# Button_Board.net
KiCad netlist of a schematic drawn in EasyEDA
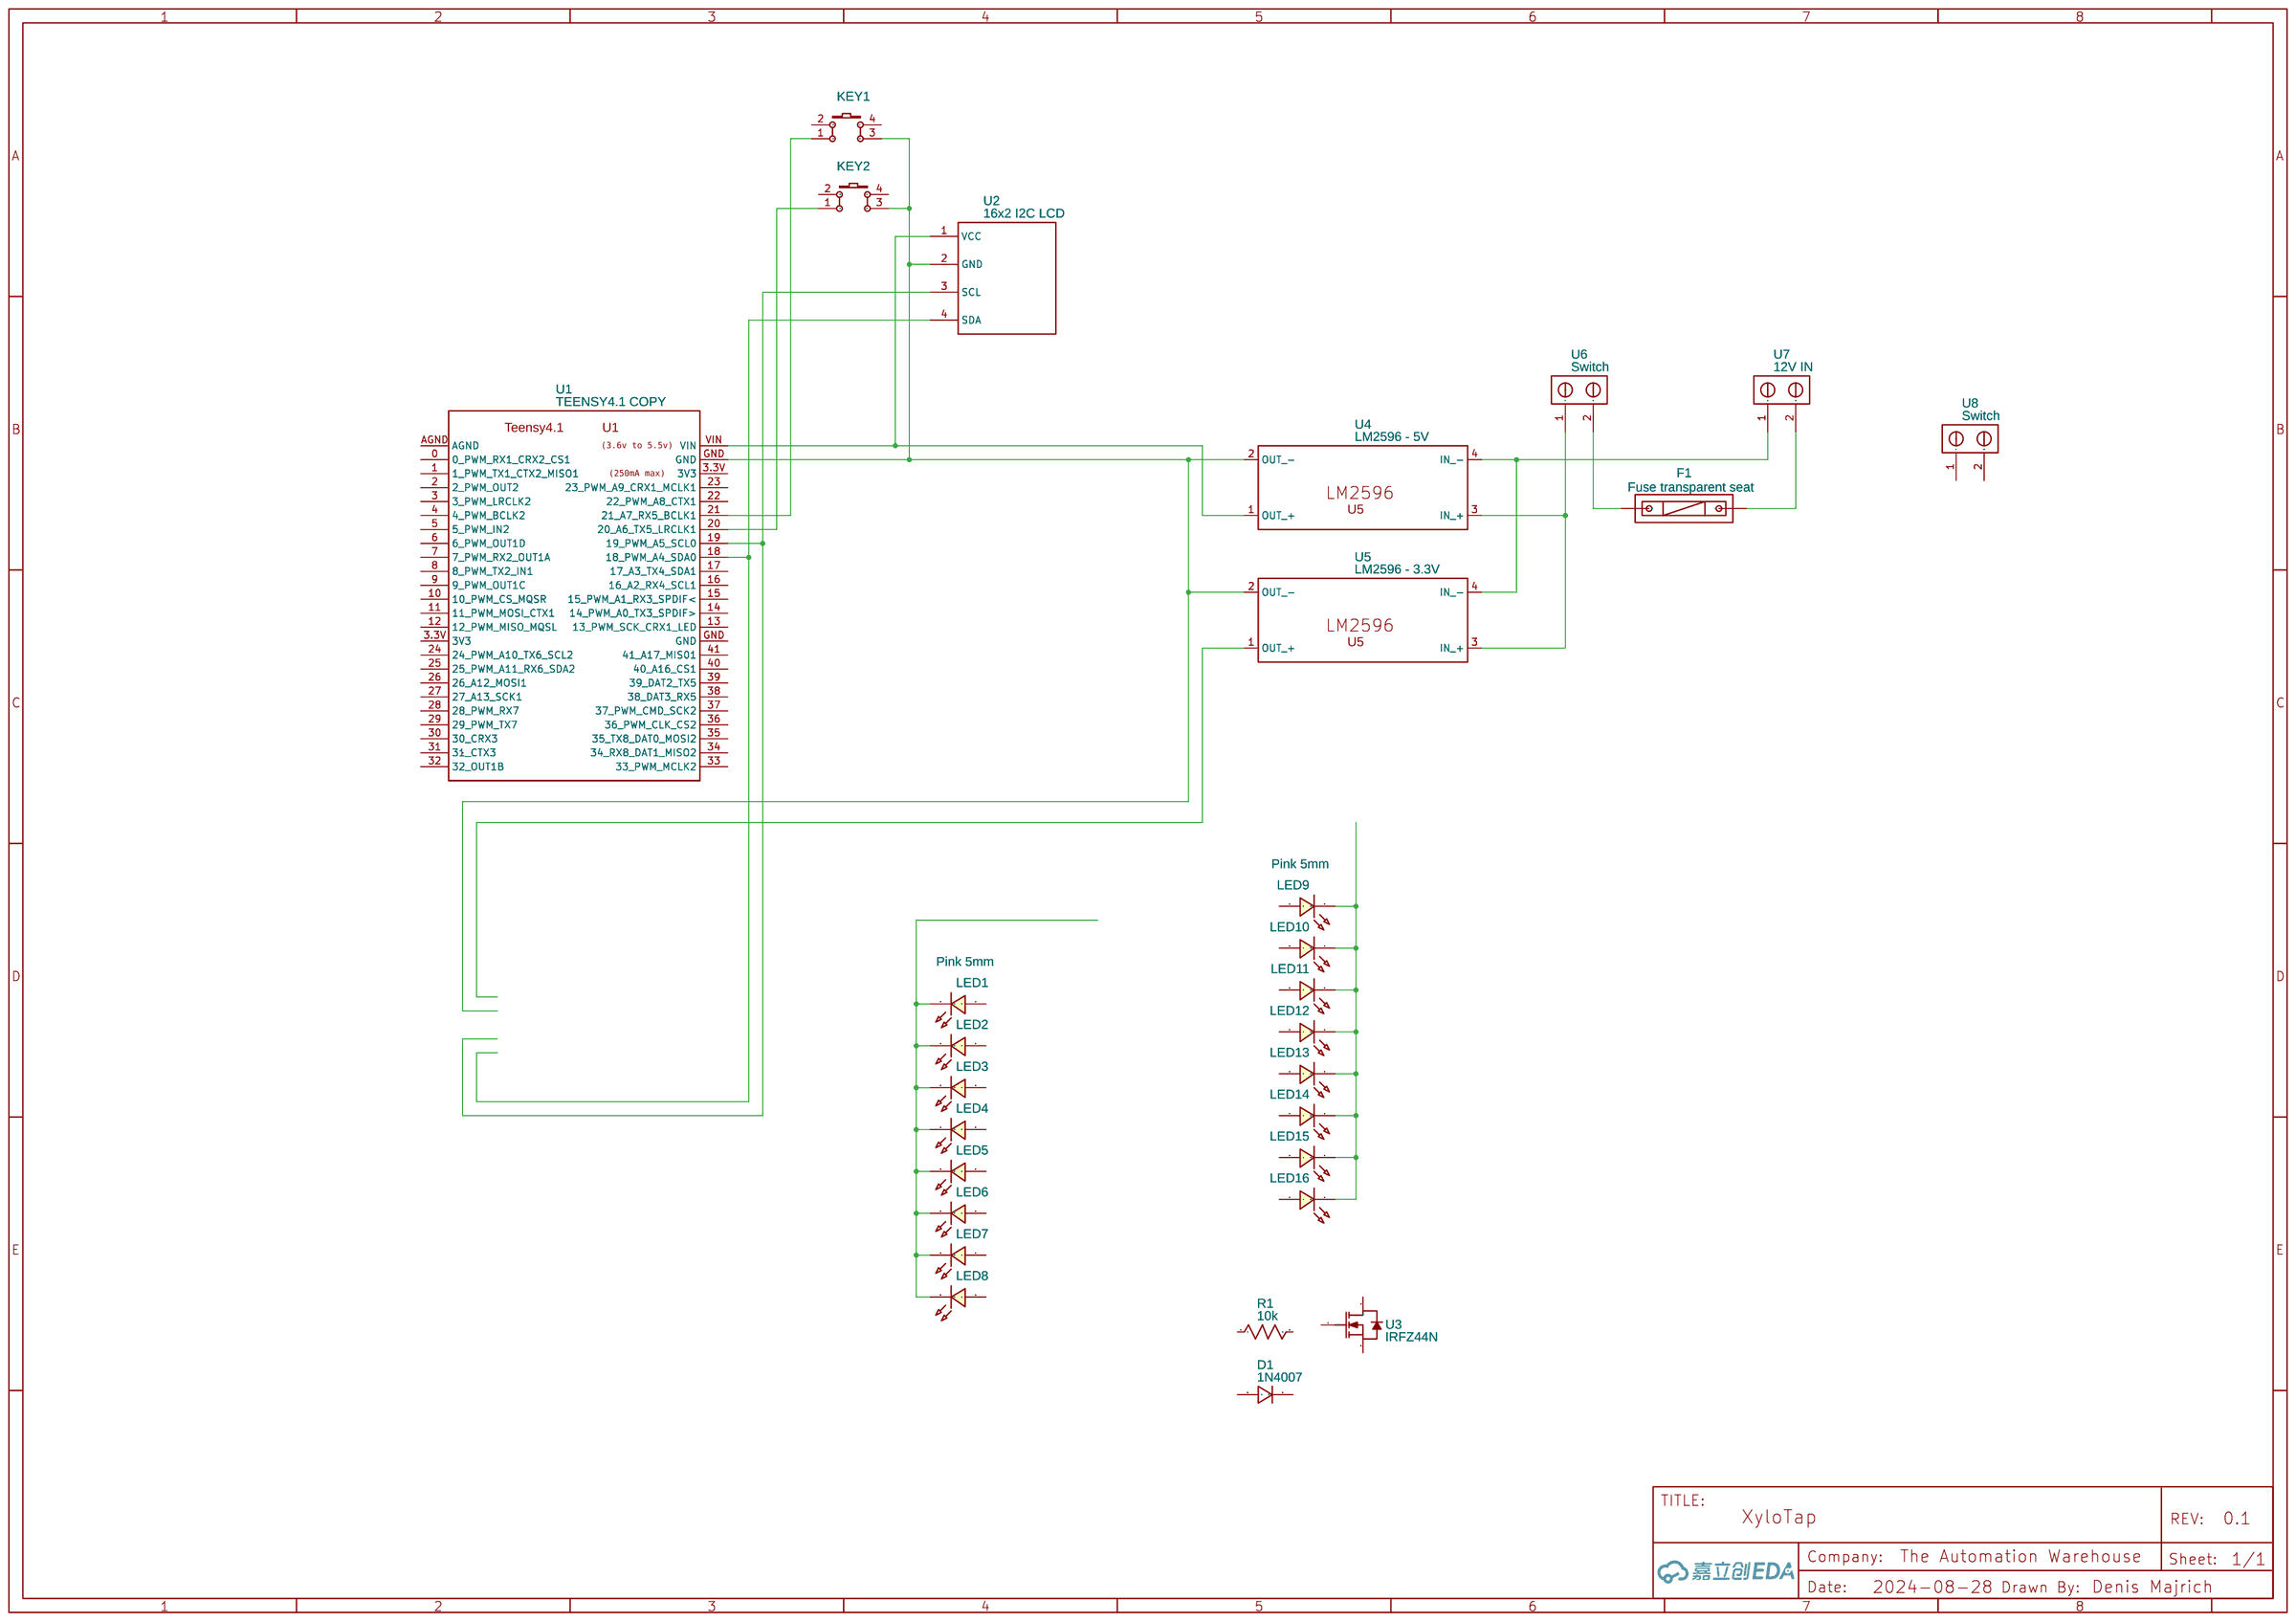
[diagram p0: Controller]
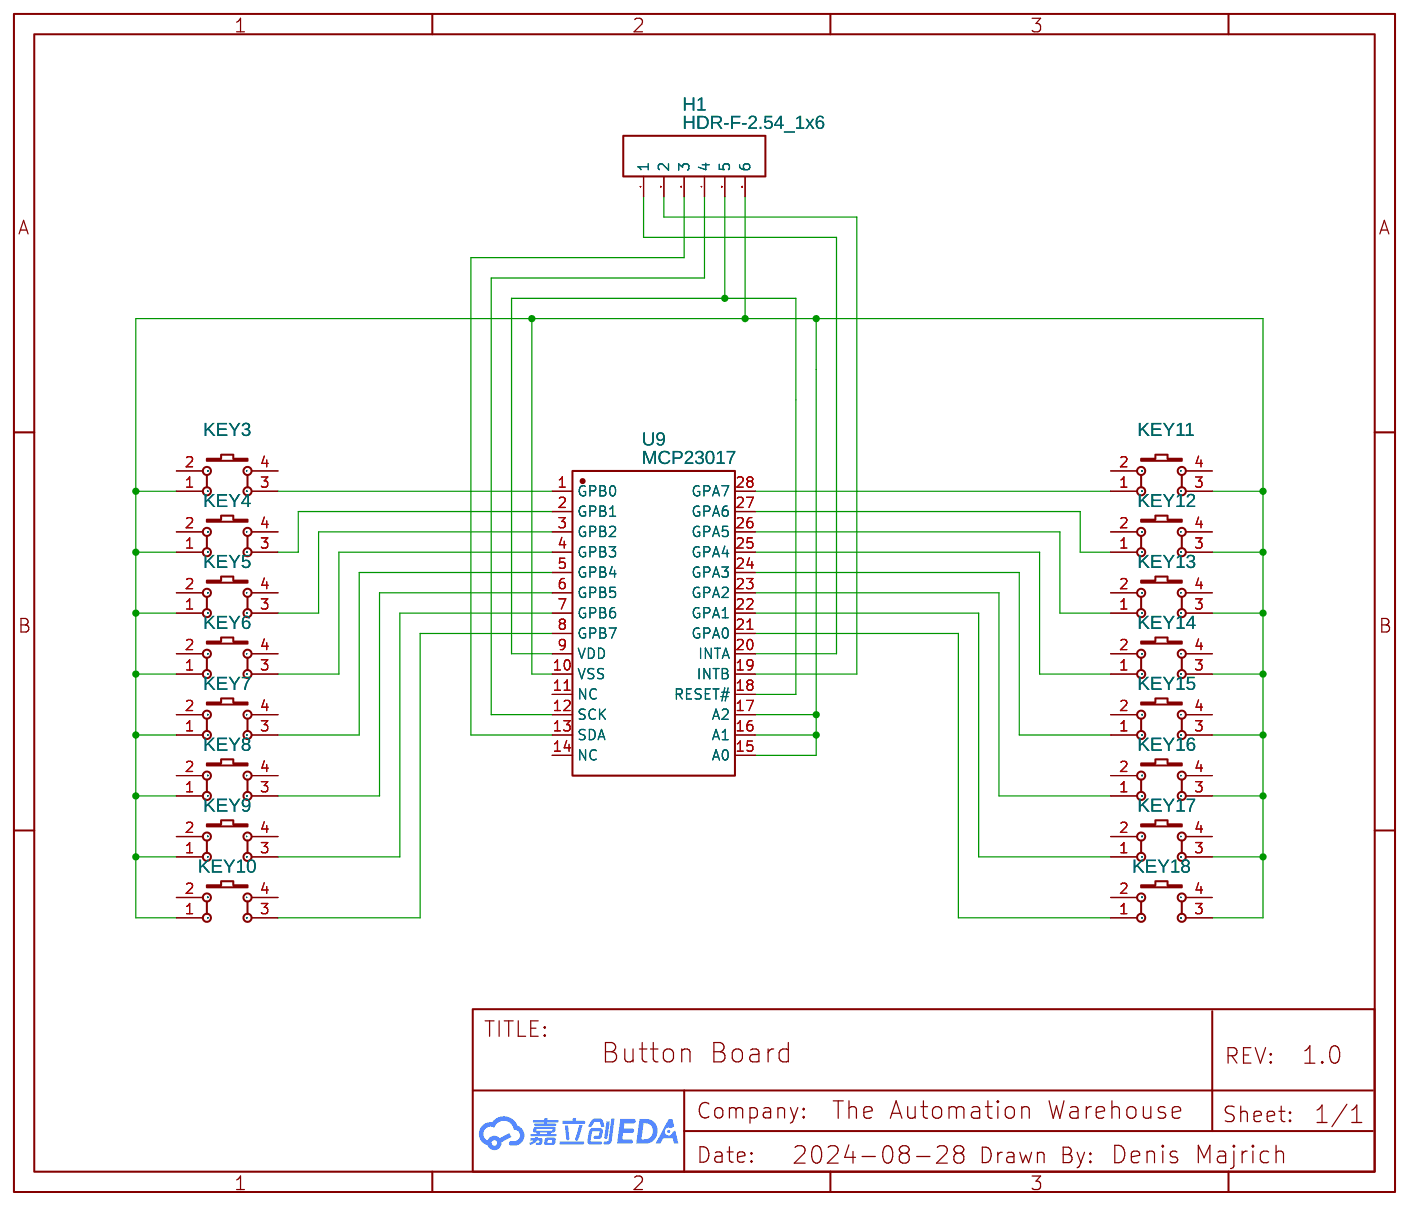
[diagram p1: Button Board]

(export (version "E")
  (design (tool "Eeschema 10.0.6"))
  (components
    (comp (ref "D1")
      (value "1N4007")
      (fields (field (name "BOM_Supplier Part") "C106903"))
      (libsource (lib "") (part "1N4007"))
    )
    (comp (ref "F1")
      (value "Fuse transparent seat")
      (fields (field (name "Manufacturer Part") "保险丝透明座") (field (name "Manufacturer") "xcfuse(旭程)"))
      (libsource (lib "") (part "Fuse transparent seat"))
    )
    (comp (ref "KEY1")
      (value "K4-12×12_TH")
      (fields
        (field (name "BOM_Manufacturer Part") "K2-1103DP-M4SW-04")
        (field (name "BOM_Supplier Part") "C128053")
      )
      (libsource (lib "") (part "K4-12×12_TH"))
    )
    (comp (ref "KEY2")
      (value "K4-12×12_TH")
      (fields
        (field (name "BOM_Manufacturer Part") "K2-1103DP-M4SW-04")
        (field (name "BOM_Supplier Part") "C128053")
      )
      (libsource (lib "") (part "K4-12×12_TH"))
    )
    (comp (ref "LED1") (value "Pink 5mm") (libsource (lib "") (part "LED-TH-5mm_B_1")))
    (comp (ref "LED2") (value "Pink 5mm") (libsource (lib "") (part "LED-TH-5mm_B_1")))
    (comp (ref "LED3") (value "Pink 5mm") (libsource (lib "") (part "LED-TH-5mm_B_1")))
    (comp (ref "LED4") (value "Pink 5mm") (libsource (lib "") (part "LED-TH-5mm_B_1")))
    (comp (ref "LED5") (value "Pink 5mm") (libsource (lib "") (part "LED-TH-5mm_B_1")))
    (comp (ref "LED6") (value "Pink 5mm") (libsource (lib "") (part "LED-TH-5mm_B_1")))
    (comp (ref "LED7") (value "Pink 5mm") (libsource (lib "") (part "LED-TH-5mm_B_1")))
    (comp (ref "LED8") (value "Pink 5mm") (libsource (lib "") (part "LED-TH-5mm_B_1")))
    (comp (ref "LED9") (value "Pink 5mm") (libsource (lib "") (part "LED-TH-5mm_B")))
    (comp (ref "LED10") (value "Pink 5mm") (libsource (lib "") (part "LED-TH-5mm_B")))
    (comp (ref "LED11") (value "Pink 5mm") (libsource (lib "") (part "LED-TH-5mm_B")))
    (comp (ref "LED12") (value "Pink 5mm") (libsource (lib "") (part "LED-TH-5mm_B")))
    (comp (ref "LED13") (value "Pink 5mm") (libsource (lib "") (part "LED-TH-5mm_B")))
    (comp (ref "LED14") (value "Pink 5mm") (libsource (lib "") (part "LED-TH-5mm_B")))
    (comp (ref "LED15") (value "Pink 5mm") (libsource (lib "") (part "LED-TH-5mm_B")))
    (comp (ref "LED16") (value "Pink 5mm") (libsource (lib "") (part "LED-TH-5mm_B")))
    (comp (ref "R1") (value "10k") (libsource (lib "") (part "R_AXIAL-0.4_US")))
    (comp (ref "U1")
      (value "TEENSY4.1 COPY")
      (fields (field (name "BOM_Manufacturer Part") "Teensy4.1"))
      (libsource (lib "") (part "TEENSY4.1 COPY"))
    )
    (comp (ref "U2") (value "16x2 I2C LCD") (libsource (lib "") (part "16x2 i2c LCD no mount on PCB")))
    (comp (ref "U3")
      (value "IRFZ44N")
      (fields (field (name "Manufacturer") "minos(迈诺斯)"))
      (libsource (lib "") (part "IRFZ44N"))
    )
    (comp (ref "U4")
      (value "LM2596 - 5V")
      (fields (field (name "BOM_Manufacturer Part") "LM2596ALEX"))
      (libsource (lib "") (part "LM2596ALEX"))
    )
    (comp (ref "U5")
      (value "LM2596 - 3.3V")
      (fields (field (name "BOM_Manufacturer Part") "LM2596ALEX"))
      (libsource (lib "") (part "LM2596ALEX"))
    )
    (comp (ref "U6") (value "Switch") (libsource (lib "") (part "Terminal_x2_5mm")))
    (comp (ref "U7") (value "12V IN") (libsource (lib "") (part "Terminal_x2_5mm")))
    (comp (ref "U8") (value "Switch") (libsource (lib "") (part "Terminal_x2_5mm")))
    (comp (ref "H1")
      (value "HDR-F-2.54_1x6")
      (fields (field (name "BOM_Supplier Part") "C40877"))
      (libsource (lib "") (part "HDR-F-2.54_1x6"))
    )
    (comp (ref "KEY3")
      (value "K4-12×12_TH")
      (fields
        (field (name "BOM_Manufacturer Part") "K2-1103DP-M4SW-04")
        (field (name "BOM_Supplier Part") "C128053")
      )
      (libsource (lib "") (part "K4-12×12_TH"))
    )
    (comp (ref "KEY4")
      (value "K4-12×12_TH")
      (fields
        (field (name "BOM_Manufacturer Part") "K2-1103DP-M4SW-04")
        (field (name "BOM_Supplier Part") "C128053")
      )
      (libsource (lib "") (part "K4-12×12_TH"))
    )
    (comp (ref "KEY5")
      (value "K4-12×12_TH")
      (fields
        (field (name "BOM_Manufacturer Part") "K2-1103DP-M4SW-04")
        (field (name "BOM_Supplier Part") "C128053")
      )
      (libsource (lib "") (part "K4-12×12_TH"))
    )
    (comp (ref "KEY6")
      (value "K4-12×12_TH")
      (fields
        (field (name "BOM_Manufacturer Part") "K2-1103DP-M4SW-04")
        (field (name "BOM_Supplier Part") "C128053")
      )
      (libsource (lib "") (part "K4-12×12_TH"))
    )
    (comp (ref "KEY7")
      (value "K4-12×12_TH")
      (fields
        (field (name "BOM_Manufacturer Part") "K2-1103DP-M4SW-04")
        (field (name "BOM_Supplier Part") "C128053")
      )
      (libsource (lib "") (part "K4-12×12_TH"))
    )
    (comp (ref "KEY8")
      (value "K4-12×12_TH")
      (fields
        (field (name "BOM_Manufacturer Part") "K2-1103DP-M4SW-04")
        (field (name "BOM_Supplier Part") "C128053")
      )
      (libsource (lib "") (part "K4-12×12_TH"))
    )
    (comp (ref "KEY9")
      (value "K4-12×12_TH")
      (fields
        (field (name "BOM_Manufacturer Part") "K2-1103DP-M4SW-04")
        (field (name "BOM_Supplier Part") "C128053")
      )
      (libsource (lib "") (part "K4-12×12_TH"))
    )
    (comp (ref "KEY10")
      (value "K4-12×12_TH")
      (fields
        (field (name "BOM_Manufacturer Part") "K2-1103DP-M4SW-04")
        (field (name "BOM_Supplier Part") "C128053")
      )
      (libsource (lib "") (part "K4-12×12_TH"))
    )
    (comp (ref "KEY11")
      (value "K4-12×12_TH")
      (fields
        (field (name "BOM_Manufacturer Part") "K2-1103DP-M4SW-04")
        (field (name "BOM_Supplier Part") "C128053")
      )
      (libsource (lib "") (part "K4-12×12_TH"))
    )
    (comp (ref "KEY12")
      (value "K4-12×12_TH")
      (fields
        (field (name "BOM_Manufacturer Part") "K2-1103DP-M4SW-04")
        (field (name "BOM_Supplier Part") "C128053")
      )
      (libsource (lib "") (part "K4-12×12_TH"))
    )
    (comp (ref "KEY13")
      (value "K4-12×12_TH")
      (fields
        (field (name "BOM_Manufacturer Part") "K2-1103DP-M4SW-04")
        (field (name "BOM_Supplier Part") "C128053")
      )
      (libsource (lib "") (part "K4-12×12_TH"))
    )
    (comp (ref "KEY14")
      (value "K4-12×12_TH")
      (fields
        (field (name "BOM_Manufacturer Part") "K2-1103DP-M4SW-04")
        (field (name "BOM_Supplier Part") "C128053")
      )
      (libsource (lib "") (part "K4-12×12_TH"))
    )
    (comp (ref "KEY15")
      (value "K4-12×12_TH")
      (fields
        (field (name "BOM_Manufacturer Part") "K2-1103DP-M4SW-04")
        (field (name "BOM_Supplier Part") "C128053")
      )
      (libsource (lib "") (part "K4-12×12_TH"))
    )
    (comp (ref "KEY16")
      (value "K4-12×12_TH")
      (fields
        (field (name "BOM_Manufacturer Part") "K2-1103DP-M4SW-04")
        (field (name "BOM_Supplier Part") "C128053")
      )
      (libsource (lib "") (part "K4-12×12_TH"))
    )
    (comp (ref "KEY17")
      (value "K4-12×12_TH")
      (fields
        (field (name "BOM_Manufacturer Part") "K2-1103DP-M4SW-04")
        (field (name "BOM_Supplier Part") "C128053")
      )
      (libsource (lib "") (part "K4-12×12_TH"))
    )
    (comp (ref "KEY18")
      (value "K4-12×12_TH")
      (fields
        (field (name "BOM_Manufacturer Part") "K2-1103DP-M4SW-04")
        (field (name "BOM_Supplier Part") "C128053")
      )
      (libsource (lib "") (part "K4-12×12_TH"))
    )
    (comp (ref "U9")
      (value "MCP23017")
      (fields
        (field (name "Manufacturer Part") "MCP23017-E/SP")
        (field (name "Manufacturer") "MICROCHIP(美国微芯)")
      )
      (libsource (lib "") (part "MCP23017-E/SP"))
    )
  )
  (nets
    (net (code "1") (name "Net-(F1-Pad1)") (class "Default")
      (node (ref "F1") (pin "1") (pinfunction "1_1") (pintype "unspecified"))
      (node (ref "U7") (pin "2") (pinfunction "2_2") (pintype "unspecified"))
    )
    (net (code "2") (name "Net-(F1-Pad2)") (class "Default")
      (node (ref "F1") (pin "2") (pinfunction "2_2") (pintype "unspecified"))
      (node (ref "U6") (pin "2") (pinfunction "2_2") (pintype "unspecified"))
    )
    (net (code "3") (name "Net-(LED1-Pad2)") (class "Default")
      (node (ref "LED1") (pin "2") (pinfunction "2_2") (pintype "unspecified"))
      (node (ref "LED2") (pin "2") (pinfunction "2_2") (pintype "unspecified"))
      (node (ref "LED3") (pin "2") (pinfunction "2_2") (pintype "unspecified"))
      (node (ref "LED4") (pin "2") (pinfunction "2_2") (pintype "unspecified"))
      (node (ref "LED5") (pin "2") (pinfunction "2_2") (pintype "unspecified"))
      (node (ref "LED6") (pin "2") (pinfunction "2_2") (pintype "unspecified"))
      (node (ref "LED7") (pin "2") (pinfunction "2_2") (pintype "unspecified"))
      (node (ref "LED8") (pin "2") (pinfunction "2_2") (pintype "unspecified"))
    )
    (net (code "4") (name "Net-(LED10-Pad2)") (class "Default")
      (node (ref "LED10") (pin "2") (pinfunction "2_2") (pintype "unspecified"))
      (node (ref "LED11") (pin "2") (pinfunction "2_2") (pintype "unspecified"))
      (node (ref "LED12") (pin "2") (pinfunction "2_2") (pintype "unspecified"))
      (node (ref "LED13") (pin "2") (pinfunction "2_2") (pintype "unspecified"))
      (node (ref "LED14") (pin "2") (pinfunction "2_2") (pintype "unspecified"))
      (node (ref "LED15") (pin "2") (pinfunction "2_2") (pintype "unspecified"))
      (node (ref "LED16") (pin "2") (pinfunction "2_2") (pintype "unspecified"))
      (node (ref "LED9") (pin "2") (pinfunction "2_2") (pintype "unspecified"))
    )
    (net (code "5") (name "Net-(U1-18_PWM_A4_SDA0)") (class "Default")
      (node (ref "U1") (pin "18") (pinfunction "18_PWM_A4_SDA0_18") (pintype "bidirectional"))
      (node (ref "U2") (pin "4") (pinfunction "SDA_4") (pintype "unspecified"))
    )
    (net (code "6") (name "Net-(U1-19_PWM_A5_SCL0)") (class "Default")
      (node (ref "U1") (pin "19") (pinfunction "19_PWM_A5_SCL0_19") (pintype "bidirectional"))
      (node (ref "U2") (pin "3") (pinfunction "SCL_3") (pintype "unspecified"))
    )
    (net (code "7") (name "Net-(U1-20_A6_TX5_LRCLK1)") (class "Default")
      (node (ref "KEY2") (pin "1") (pinfunction "1_1") (pintype "unspecified"))
      (node (ref "U1") (pin "20") (pinfunction "20_A6_TX5_LRCLK1_20") (pintype "bidirectional"))
    )
    (net (code "8") (name "Net-(U1-21_A7_RX5_BCLK1)") (class "Default")
      (node (ref "KEY1") (pin "1") (pinfunction "1_1") (pintype "unspecified"))
      (node (ref "U1") (pin "21") (pinfunction "21_A7_RX5_BCLK1_21") (pintype "bidirectional"))
    )
    (net (code "9") (name "Net-(U2-GND)") (class "Default")
      (node (ref "KEY1") (pin "3") (pinfunction "3_3") (pintype "unspecified"))
      (node (ref "KEY2") (pin "3") (pinfunction "3_3") (pintype "unspecified"))
      (node (ref "U1") (pin "GND") (pinfunction "GND_GND") (pintype "bidirectional"))
      (node (ref "U2") (pin "2") (pinfunction "GND_2") (pintype "unspecified"))
      (node (ref "U4") (pin "2") (pinfunction "OUT_-_2") (pintype "unspecified"))
      (node (ref "U5") (pin "2") (pinfunction "OUT_-_2") (pintype "unspecified"))
    )
    (net (code "10") (name "Net-(U2-VCC)") (class "Default")
      (node (ref "U1") (pin "VIN") (pinfunction "VIN_VIN") (pintype "bidirectional"))
      (node (ref "U2") (pin "1") (pinfunction "VCC_1") (pintype "unspecified"))
      (node (ref "U4") (pin "1") (pinfunction "OUT_+_1") (pintype "unspecified"))
    )
    (net (code "11") (name "Net-(U4-IN_+)") (class "Default")
      (node (ref "U4") (pin "3") (pinfunction "IN_+_3") (pintype "unspecified"))
      (node (ref "U5") (pin "3") (pinfunction "IN_+_3") (pintype "unspecified"))
      (node (ref "U6") (pin "1") (pinfunction "1_1") (pintype "unspecified"))
    )
    (net (code "12") (name "Net-(U4-IN_-)") (class "Default")
      (node (ref "U4") (pin "4") (pinfunction "IN_-_4") (pintype "unspecified"))
      (node (ref "U5") (pin "4") (pinfunction "IN_-_4") (pintype "unspecified"))
      (node (ref "U7") (pin "1") (pinfunction "1_1") (pintype "unspecified"))
    )
    (net (code "13") (name "Net-(U9-A0)") (class "Default")
      (node (ref "H1") (pin "6") (pinfunction "6_6") (pintype "input"))
      (node (ref "KEY10") (pin "1") (pinfunction "1_1") (pintype "unspecified"))
      (node (ref "KEY11") (pin "3") (pinfunction "3_3") (pintype "unspecified"))
      (node (ref "KEY12") (pin "3") (pinfunction "3_3") (pintype "unspecified"))
      (node (ref "KEY13") (pin "3") (pinfunction "3_3") (pintype "unspecified"))
      (node (ref "KEY14") (pin "3") (pinfunction "3_3") (pintype "unspecified"))
      (node (ref "KEY15") (pin "3") (pinfunction "3_3") (pintype "unspecified"))
      (node (ref "KEY16") (pin "3") (pinfunction "3_3") (pintype "unspecified"))
      (node (ref "KEY17") (pin "3") (pinfunction "3_3") (pintype "unspecified"))
      (node (ref "KEY18") (pin "3") (pinfunction "3_3") (pintype "unspecified"))
      (node (ref "KEY3") (pin "1") (pinfunction "1_1") (pintype "unspecified"))
      (node (ref "KEY4") (pin "1") (pinfunction "1_1") (pintype "unspecified"))
      (node (ref "KEY5") (pin "1") (pinfunction "1_1") (pintype "unspecified"))
      (node (ref "KEY6") (pin "1") (pinfunction "1_1") (pintype "unspecified"))
      (node (ref "KEY7") (pin "1") (pinfunction "1_1") (pintype "unspecified"))
      (node (ref "KEY8") (pin "1") (pinfunction "1_1") (pintype "unspecified"))
      (node (ref "KEY9") (pin "1") (pinfunction "1_1") (pintype "unspecified"))
      (node (ref "U9") (pin "10") (pinfunction "VSS_10") (pintype "unspecified"))
      (node (ref "U9") (pin "15") (pinfunction "A0_15") (pintype "unspecified"))
      (node (ref "U9") (pin "16") (pinfunction "A1_16") (pintype "unspecified"))
      (node (ref "U9") (pin "17") (pinfunction "A2_17") (pintype "unspecified"))
    )
    (net (code "14") (name "Net-(U9-GPA0)") (class "Default")
      (node (ref "KEY18") (pin "1") (pinfunction "1_1") (pintype "unspecified"))
      (node (ref "U9") (pin "21") (pinfunction "GPA0_21") (pintype "unspecified"))
    )
    (net (code "15") (name "Net-(U9-GPA1)") (class "Default")
      (node (ref "KEY17") (pin "1") (pinfunction "1_1") (pintype "unspecified"))
      (node (ref "U9") (pin "22") (pinfunction "GPA1_22") (pintype "unspecified"))
    )
    (net (code "16") (name "Net-(U9-GPA2)") (class "Default")
      (node (ref "KEY16") (pin "1") (pinfunction "1_1") (pintype "unspecified"))
      (node (ref "U9") (pin "23") (pinfunction "GPA2_23") (pintype "unspecified"))
    )
    (net (code "17") (name "Net-(U9-GPA3)") (class "Default")
      (node (ref "KEY15") (pin "1") (pinfunction "1_1") (pintype "unspecified"))
      (node (ref "U9") (pin "24") (pinfunction "GPA3_24") (pintype "unspecified"))
    )
    (net (code "18") (name "Net-(U9-GPA4)") (class "Default")
      (node (ref "KEY14") (pin "1") (pinfunction "1_1") (pintype "unspecified"))
      (node (ref "U9") (pin "25") (pinfunction "GPA4_25") (pintype "unspecified"))
    )
    (net (code "19") (name "Net-(U9-GPA5)") (class "Default")
      (node (ref "KEY13") (pin "1") (pinfunction "1_1") (pintype "unspecified"))
      (node (ref "U9") (pin "26") (pinfunction "GPA5_26") (pintype "unspecified"))
    )
    (net (code "20") (name "Net-(U9-GPA6)") (class "Default")
      (node (ref "KEY12") (pin "1") (pinfunction "1_1") (pintype "unspecified"))
      (node (ref "U9") (pin "27") (pinfunction "GPA6_27") (pintype "unspecified"))
    )
    (net (code "21") (name "Net-(U9-GPA7)") (class "Default")
      (node (ref "KEY11") (pin "1") (pinfunction "1_1") (pintype "unspecified"))
      (node (ref "U9") (pin "28") (pinfunction "GPA7_28") (pintype "unspecified"))
    )
    (net (code "22") (name "Net-(U9-GPB0)") (class "Default")
      (node (ref "KEY3") (pin "3") (pinfunction "3_3") (pintype "unspecified"))
      (node (ref "U9") (pin "1") (pinfunction "GPB0_1") (pintype "unspecified"))
    )
    (net (code "23") (name "Net-(U9-GPB1)") (class "Default")
      (node (ref "KEY4") (pin "3") (pinfunction "3_3") (pintype "unspecified"))
      (node (ref "U9") (pin "2") (pinfunction "GPB1_2") (pintype "unspecified"))
    )
    (net (code "24") (name "Net-(U9-GPB2)") (class "Default")
      (node (ref "KEY5") (pin "3") (pinfunction "3_3") (pintype "unspecified"))
      (node (ref "U9") (pin "3") (pinfunction "GPB2_3") (pintype "unspecified"))
    )
    (net (code "25") (name "Net-(U9-GPB3)") (class "Default")
      (node (ref "KEY6") (pin "3") (pinfunction "3_3") (pintype "unspecified"))
      (node (ref "U9") (pin "4") (pinfunction "GPB3_4") (pintype "unspecified"))
    )
    (net (code "26") (name "Net-(U9-GPB4)") (class "Default")
      (node (ref "KEY7") (pin "3") (pinfunction "3_3") (pintype "unspecified"))
      (node (ref "U9") (pin "5") (pinfunction "GPB4_5") (pintype "unspecified"))
    )
    (net (code "27") (name "Net-(U9-GPB5)") (class "Default")
      (node (ref "KEY8") (pin "3") (pinfunction "3_3") (pintype "unspecified"))
      (node (ref "U9") (pin "6") (pinfunction "GPB5_6") (pintype "unspecified"))
    )
    (net (code "28") (name "Net-(U9-GPB6)") (class "Default")
      (node (ref "KEY9") (pin "3") (pinfunction "3_3") (pintype "unspecified"))
      (node (ref "U9") (pin "7") (pinfunction "GPB6_7") (pintype "unspecified"))
    )
    (net (code "29") (name "Net-(U9-GPB7)") (class "Default")
      (node (ref "KEY10") (pin "3") (pinfunction "3_3") (pintype "unspecified"))
      (node (ref "U9") (pin "8") (pinfunction "GPB7_8") (pintype "unspecified"))
    )
    (net (code "30") (name "Net-(U9-INTA)") (class "Default")
      (node (ref "H1") (pin "1") (pinfunction "1_1") (pintype "input"))
      (node (ref "U9") (pin "20") (pinfunction "INTA_20") (pintype "unspecified"))
    )
    (net (code "31") (name "Net-(U9-INTB)") (class "Default")
      (node (ref "H1") (pin "2") (pinfunction "2_2") (pintype "input"))
      (node (ref "U9") (pin "19") (pinfunction "INTB_19") (pintype "unspecified"))
    )
    (net (code "32") (name "Net-(U9-RESET#)") (class "Default")
      (node (ref "H1") (pin "5") (pinfunction "5_5") (pintype "input"))
      (node (ref "U9") (pin "18") (pinfunction "RESET#_18") (pintype "unspecified"))
      (node (ref "U9") (pin "9") (pinfunction "VDD_9") (pintype "unspecified"))
    )
    (net (code "33") (name "Net-(U9-SCK)") (class "Default")
      (node (ref "H1") (pin "4") (pinfunction "4_4") (pintype "input"))
      (node (ref "U9") (pin "12") (pinfunction "SCK_12") (pintype "unspecified"))
    )
    (net (code "34") (name "Net-(U9-SDA)") (class "Default")
      (node (ref "H1") (pin "3") (pinfunction "3_3") (pintype "input"))
      (node (ref "U9") (pin "13") (pinfunction "SDA_13") (pintype "unspecified"))
    )
    (net (code "35") (name "unconnected-(D1-Pad1)") (class "Default")
      (node (ref "D1") (pin "1") (pinfunction "1_1") (pintype "unspecified"))
    )
    (net (code "36") (name "unconnected-(D1-Pad2)") (class "Default")
      (node (ref "D1") (pin "2") (pinfunction "2_2") (pintype "unspecified"))
    )
    (net (code "37") (name "unconnected-(KEY1-Pad2)") (class "Default")
      (node (ref "KEY1") (pin "2") (pinfunction "2_2") (pintype "unspecified"))
    )
    (net (code "38") (name "unconnected-(KEY1-Pad4)") (class "Default")
      (node (ref "KEY1") (pin "4") (pinfunction "4_4") (pintype "unspecified"))
    )
    (net (code "39") (name "unconnected-(KEY2-Pad2)") (class "Default")
      (node (ref "KEY2") (pin "2") (pinfunction "2_2") (pintype "unspecified"))
    )
    (net (code "40") (name "unconnected-(KEY2-Pad4)") (class "Default")
      (node (ref "KEY2") (pin "4") (pinfunction "4_4") (pintype "unspecified"))
    )
    (net (code "41") (name "unconnected-(KEY3-Pad2)") (class "Default")
      (node (ref "KEY3") (pin "2") (pinfunction "2_2") (pintype "unspecified"))
    )
    (net (code "42") (name "unconnected-(KEY3-Pad4)") (class "Default")
      (node (ref "KEY3") (pin "4") (pinfunction "4_4") (pintype "unspecified"))
    )
    (net (code "43") (name "unconnected-(KEY4-Pad2)") (class "Default")
      (node (ref "KEY4") (pin "2") (pinfunction "2_2") (pintype "unspecified"))
    )
    (net (code "44") (name "unconnected-(KEY4-Pad4)") (class "Default")
      (node (ref "KEY4") (pin "4") (pinfunction "4_4") (pintype "unspecified"))
    )
    (net (code "45") (name "unconnected-(KEY5-Pad2)") (class "Default")
      (node (ref "KEY5") (pin "2") (pinfunction "2_2") (pintype "unspecified"))
    )
    (net (code "46") (name "unconnected-(KEY5-Pad4)") (class "Default")
      (node (ref "KEY5") (pin "4") (pinfunction "4_4") (pintype "unspecified"))
    )
    (net (code "47") (name "unconnected-(KEY6-Pad2)") (class "Default")
      (node (ref "KEY6") (pin "2") (pinfunction "2_2") (pintype "unspecified"))
    )
    (net (code "48") (name "unconnected-(KEY6-Pad4)") (class "Default")
      (node (ref "KEY6") (pin "4") (pinfunction "4_4") (pintype "unspecified"))
    )
    (net (code "49") (name "unconnected-(KEY7-Pad2)") (class "Default")
      (node (ref "KEY7") (pin "2") (pinfunction "2_2") (pintype "unspecified"))
    )
    (net (code "50") (name "unconnected-(KEY7-Pad4)") (class "Default")
      (node (ref "KEY7") (pin "4") (pinfunction "4_4") (pintype "unspecified"))
    )
    (net (code "51") (name "unconnected-(KEY8-Pad2)") (class "Default")
      (node (ref "KEY8") (pin "2") (pinfunction "2_2") (pintype "unspecified"))
    )
    (net (code "52") (name "unconnected-(KEY8-Pad4)") (class "Default")
      (node (ref "KEY8") (pin "4") (pinfunction "4_4") (pintype "unspecified"))
    )
    (net (code "53") (name "unconnected-(KEY9-Pad2)") (class "Default")
      (node (ref "KEY9") (pin "2") (pinfunction "2_2") (pintype "unspecified"))
    )
    (net (code "54") (name "unconnected-(KEY9-Pad4)") (class "Default")
      (node (ref "KEY9") (pin "4") (pinfunction "4_4") (pintype "unspecified"))
    )
    (net (code "55") (name "unconnected-(KEY10-Pad2)") (class "Default")
      (node (ref "KEY10") (pin "2") (pinfunction "2_2") (pintype "unspecified"))
    )
    (net (code "56") (name "unconnected-(KEY10-Pad4)") (class "Default")
      (node (ref "KEY10") (pin "4") (pinfunction "4_4") (pintype "unspecified"))
    )
    (net (code "57") (name "unconnected-(KEY11-Pad2)") (class "Default")
      (node (ref "KEY11") (pin "2") (pinfunction "2_2") (pintype "unspecified"))
    )
    (net (code "58") (name "unconnected-(KEY11-Pad4)") (class "Default")
      (node (ref "KEY11") (pin "4") (pinfunction "4_4") (pintype "unspecified"))
    )
    (net (code "59") (name "unconnected-(KEY12-Pad2)") (class "Default")
      (node (ref "KEY12") (pin "2") (pinfunction "2_2") (pintype "unspecified"))
    )
    (net (code "60") (name "unconnected-(KEY12-Pad4)") (class "Default")
      (node (ref "KEY12") (pin "4") (pinfunction "4_4") (pintype "unspecified"))
    )
    (net (code "61") (name "unconnected-(KEY13-Pad2)") (class "Default")
      (node (ref "KEY13") (pin "2") (pinfunction "2_2") (pintype "unspecified"))
    )
    (net (code "62") (name "unconnected-(KEY13-Pad4)") (class "Default")
      (node (ref "KEY13") (pin "4") (pinfunction "4_4") (pintype "unspecified"))
    )
    (net (code "63") (name "unconnected-(KEY14-Pad2)") (class "Default")
      (node (ref "KEY14") (pin "2") (pinfunction "2_2") (pintype "unspecified"))
    )
    (net (code "64") (name "unconnected-(KEY14-Pad4)") (class "Default")
      (node (ref "KEY14") (pin "4") (pinfunction "4_4") (pintype "unspecified"))
    )
    (net (code "65") (name "unconnected-(KEY15-Pad2)") (class "Default")
      (node (ref "KEY15") (pin "2") (pinfunction "2_2") (pintype "unspecified"))
    )
    (net (code "66") (name "unconnected-(KEY15-Pad4)") (class "Default")
      (node (ref "KEY15") (pin "4") (pinfunction "4_4") (pintype "unspecified"))
    )
    (net (code "67") (name "unconnected-(KEY16-Pad2)") (class "Default")
      (node (ref "KEY16") (pin "2") (pinfunction "2_2") (pintype "unspecified"))
    )
    (net (code "68") (name "unconnected-(KEY16-Pad4)") (class "Default")
      (node (ref "KEY16") (pin "4") (pinfunction "4_4") (pintype "unspecified"))
    )
    (net (code "69") (name "unconnected-(KEY17-Pad2)") (class "Default")
      (node (ref "KEY17") (pin "2") (pinfunction "2_2") (pintype "unspecified"))
    )
    (net (code "70") (name "unconnected-(KEY17-Pad4)") (class "Default")
      (node (ref "KEY17") (pin "4") (pinfunction "4_4") (pintype "unspecified"))
    )
    (net (code "71") (name "unconnected-(KEY18-Pad2)") (class "Default")
      (node (ref "KEY18") (pin "2") (pinfunction "2_2") (pintype "unspecified"))
    )
    (net (code "72") (name "unconnected-(KEY18-Pad4)") (class "Default")
      (node (ref "KEY18") (pin "4") (pinfunction "4_4") (pintype "unspecified"))
    )
    (net (code "73") (name "unconnected-(LED1-Pad1)") (class "Default")
      (node (ref "LED1") (pin "1") (pinfunction "1_1") (pintype "unspecified"))
    )
    (net (code "74") (name "unconnected-(LED2-Pad1)") (class "Default")
      (node (ref "LED2") (pin "1") (pinfunction "1_1") (pintype "unspecified"))
    )
    (net (code "75") (name "unconnected-(LED3-Pad1)") (class "Default")
      (node (ref "LED3") (pin "1") (pinfunction "1_1") (pintype "unspecified"))
    )
    (net (code "76") (name "unconnected-(LED4-Pad1)") (class "Default")
      (node (ref "LED4") (pin "1") (pinfunction "1_1") (pintype "unspecified"))
    )
    (net (code "77") (name "unconnected-(LED5-Pad1)") (class "Default")
      (node (ref "LED5") (pin "1") (pinfunction "1_1") (pintype "unspecified"))
    )
    (net (code "78") (name "unconnected-(LED6-Pad1)") (class "Default")
      (node (ref "LED6") (pin "1") (pinfunction "1_1") (pintype "unspecified"))
    )
    (net (code "79") (name "unconnected-(LED7-Pad1)") (class "Default")
      (node (ref "LED7") (pin "1") (pinfunction "1_1") (pintype "unspecified"))
    )
    (net (code "80") (name "unconnected-(LED8-Pad1)") (class "Default")
      (node (ref "LED8") (pin "1") (pinfunction "1_1") (pintype "unspecified"))
    )
    (net (code "81") (name "unconnected-(LED9-Pad1)") (class "Default")
      (node (ref "LED9") (pin "1") (pinfunction "1_1") (pintype "unspecified"))
    )
    (net (code "82") (name "unconnected-(LED10-Pad1)") (class "Default")
      (node (ref "LED10") (pin "1") (pinfunction "1_1") (pintype "unspecified"))
    )
    (net (code "83") (name "unconnected-(LED11-Pad1)") (class "Default")
      (node (ref "LED11") (pin "1") (pinfunction "1_1") (pintype "unspecified"))
    )
    (net (code "84") (name "unconnected-(LED12-Pad1)") (class "Default")
      (node (ref "LED12") (pin "1") (pinfunction "1_1") (pintype "unspecified"))
    )
    (net (code "85") (name "unconnected-(LED13-Pad1)") (class "Default")
      (node (ref "LED13") (pin "1") (pinfunction "1_1") (pintype "unspecified"))
    )
    (net (code "86") (name "unconnected-(LED14-Pad1)") (class "Default")
      (node (ref "LED14") (pin "1") (pinfunction "1_1") (pintype "unspecified"))
    )
    (net (code "87") (name "unconnected-(LED15-Pad1)") (class "Default")
      (node (ref "LED15") (pin "1") (pinfunction "1_1") (pintype "unspecified"))
    )
    (net (code "88") (name "unconnected-(LED16-Pad1)") (class "Default")
      (node (ref "LED16") (pin "1") (pinfunction "1_1") (pintype "unspecified"))
    )
    (net (code "89") (name "unconnected-(R1-Pad1)") (class "Default")
      (node (ref "R1") (pin "1") (pinfunction "1_1") (pintype "unspecified"))
    )
    (net (code "90") (name "unconnected-(R1-Pad2)") (class "Default")
      (node (ref "R1") (pin "2") (pinfunction "2_2") (pintype "unspecified"))
    )
    (net (code "91") (name "unconnected-(U1-0_PWM_RX1_CRX2_CS1-Pad0)") (class "Default")
      (node (ref "U1") (pin "0") (pinfunction "0_PWM_RX1_CRX2_CS1_0") (pintype "bidirectional"))
    )
    (net (code "92") (name "unconnected-(U1-1_PWM_TX1_CTX2_MISO1-Pad1)") (class "Default")
      (node (ref "U1") (pin "1") (pinfunction "1_PWM_TX1_CTX2_MISO1_1") (pintype "bidirectional"))
    )
    (net (code "93") (name "unconnected-(U1-2_PWM_OUT2-Pad2)") (class "Default")
      (node (ref "U1") (pin "2") (pinfunction "2_PWM_OUT2_2") (pintype "bidirectional"))
    )
    (net (code "94") (name "unconnected-(U1-3V3-Pad3.3V)") (class "Default")
      (node (ref "U1") (pin "3.3V") (pinfunction "3V3_3.3V") (pintype "bidirectional"))
    )
    (net (code "95") (name "unconnected-(U1-3V3-Pad3.3V)_1") (class "Default")
      (node (ref "U1") (pin "3.3V") (pinfunction "3V3_3.3V") (pintype "bidirectional"))
    )
    (net (code "96") (name "unconnected-(U1-3_PWM_LRCLK2-Pad3)") (class "Default")
      (node (ref "U1") (pin "3") (pinfunction "3_PWM_LRCLK2_3") (pintype "bidirectional"))
    )
    (net (code "97") (name "unconnected-(U1-4_PWM_BCLK2-Pad4)") (class "Default")
      (node (ref "U1") (pin "4") (pinfunction "4_PWM_BCLK2_4") (pintype "bidirectional"))
    )
    (net (code "98") (name "unconnected-(U1-5_PWM_IN2-Pad5)") (class "Default")
      (node (ref "U1") (pin "5") (pinfunction "5_PWM_IN2_5") (pintype "bidirectional"))
    )
    (net (code "99") (name "unconnected-(U1-6_PWM_OUT1D-Pad6)") (class "Default")
      (node (ref "U1") (pin "6") (pinfunction "6_PWM_OUT1D_6") (pintype "bidirectional"))
    )
    (net (code "100") (name "unconnected-(U1-7_PWM_RX2_OUT1A-Pad7)") (class "Default")
      (node (ref "U1") (pin "7") (pinfunction "7_PWM_RX2_OUT1A_7") (pintype "bidirectional"))
    )
    (net (code "101") (name "unconnected-(U1-8_PWM_TX2_IN1-Pad8)") (class "Default")
      (node (ref "U1") (pin "8") (pinfunction "8_PWM_TX2_IN1_8") (pintype "bidirectional"))
    )
    (net (code "102") (name "unconnected-(U1-9_PWM_OUT1C-Pad9)") (class "Default")
      (node (ref "U1") (pin "9") (pinfunction "9_PWM_OUT1C_9") (pintype "bidirectional"))
    )
    (net (code "103") (name "unconnected-(U1-10_PWM_CS_MQSR-Pad10)") (class "Default")
      (node (ref "U1") (pin "10") (pinfunction "10_PWM_CS_MQSR_10") (pintype "bidirectional"))
    )
    (net (code "104") (name "unconnected-(U1-11_PWM_MOSI_CTX1-Pad11)") (class "Default")
      (node (ref "U1") (pin "11") (pinfunction "11_PWM_MOSI_CTX1_11") (pintype "bidirectional"))
    )
    (net (code "105") (name "unconnected-(U1-12_PWM_MISO_MQSL-Pad12)") (class "Default")
      (node (ref "U1") (pin "12") (pinfunction "12_PWM_MISO_MQSL_12") (pintype "bidirectional"))
    )
    (net (code "106") (name "unconnected-(U1-13_PWM_SCK_CRX1_LED-Pad13)") (class "Default")
      (node (ref "U1") (pin "13") (pinfunction "13_PWM_SCK_CRX1_LED_13") (pintype "bidirectional"))
    )
    (net (code "107") (name "unconnected-(U1-14_PWM_A0_TX3_SPDIF>-Pad14)") (class "Default")
      (node (ref "U1") (pin "14") (pinfunction "14_PWM_A0_TX3_SPDIF>_14") (pintype "bidirectional"))
    )
    (net (code "108") (name "unconnected-(U1-15_PWM_A1_RX3_SPDIF<-Pad15)") (class "Default")
      (node (ref "U1") (pin "15") (pinfunction "15_PWM_A1_RX3_SPDIF<_15") (pintype "bidirectional"))
    )
    (net (code "109") (name "unconnected-(U1-16_A2_RX4_SCL1-Pad16)") (class "Default")
      (node (ref "U1") (pin "16") (pinfunction "16_A2_RX4_SCL1_16") (pintype "bidirectional"))
    )
    (net (code "110") (name "unconnected-(U1-17_A3_TX4_SDA1-Pad17)") (class "Default")
      (node (ref "U1") (pin "17") (pinfunction "17_A3_TX4_SDA1_17") (pintype "bidirectional"))
    )
    (net (code "111") (name "unconnected-(U1-22_PWM_A8_CTX1-Pad22)") (class "Default")
      (node (ref "U1") (pin "22") (pinfunction "22_PWM_A8_CTX1_22") (pintype "bidirectional"))
    )
    (net (code "112") (name "unconnected-(U1-23_PWM_A9_CRX1_MCLK1-Pad23)") (class "Default")
      (node (ref "U1") (pin "23") (pinfunction "23_PWM_A9_CRX1_MCLK1_23") (pintype "bidirectional"))
    )
    (net (code "113") (name "unconnected-(U1-24_PWM_A10_TX6_SCL2-Pad24)") (class "Default")
      (node (ref "U1") (pin "24") (pinfunction "24_PWM_A10_TX6_SCL2_24") (pintype "bidirectional"))
    )
    (net (code "114") (name "unconnected-(U1-25_PWM_A11_RX6_SDA2-Pad25)") (class "Default")
      (node (ref "U1") (pin "25") (pinfunction "25_PWM_A11_RX6_SDA2_25") (pintype "bidirectional"))
    )
    (net (code "115") (name "unconnected-(U1-26_A12_MOSI1-Pad26)") (class "Default")
      (node (ref "U1") (pin "26") (pinfunction "26_A12_MOSI1_26") (pintype "bidirectional"))
    )
    (net (code "116") (name "unconnected-(U1-27_A13_SCK1-Pad27)") (class "Default")
      (node (ref "U1") (pin "27") (pinfunction "27_A13_SCK1_27") (pintype "bidirectional"))
    )
    (net (code "117") (name "unconnected-(U1-28_PWM_RX7-Pad28)") (class "Default")
      (node (ref "U1") (pin "28") (pinfunction "28_PWM_RX7_28") (pintype "bidirectional"))
    )
    (net (code "118") (name "unconnected-(U1-29_PWM_TX7-Pad29)") (class "Default")
      (node (ref "U1") (pin "29") (pinfunction "29_PWM_TX7_29") (pintype "bidirectional"))
    )
    (net (code "119") (name "unconnected-(U1-30_CRX3-Pad30)") (class "Default")
      (node (ref "U1") (pin "30") (pinfunction "30_CRX3_30") (pintype "bidirectional"))
    )
    (net (code "120") (name "unconnected-(U1-31_CTX3-Pad31)") (class "Default")
      (node (ref "U1") (pin "31") (pinfunction "31_CTX3_31") (pintype "bidirectional"))
    )
    (net (code "121") (name "unconnected-(U1-32_OUT1B-Pad32)") (class "Default")
      (node (ref "U1") (pin "32") (pinfunction "32_OUT1B_32") (pintype "bidirectional"))
    )
    (net (code "122") (name "unconnected-(U1-33_PWM_MCLK2-Pad33)") (class "Default")
      (node (ref "U1") (pin "33") (pinfunction "33_PWM_MCLK2_33") (pintype "bidirectional"))
    )
    (net (code "123") (name "unconnected-(U1-34_RX8_DAT1_MISO2-Pad34)") (class "Default")
      (node (ref "U1") (pin "34") (pinfunction "34_RX8_DAT1_MISO2_34") (pintype "bidirectional"))
    )
    (net (code "124") (name "unconnected-(U1-35_TX8_DAT0_MOSI2-Pad35)") (class "Default")
      (node (ref "U1") (pin "35") (pinfunction "35_TX8_DAT0_MOSI2_35") (pintype "bidirectional"))
    )
    (net (code "125") (name "unconnected-(U1-36_PWM_CLK_CS2-Pad36)") (class "Default")
      (node (ref "U1") (pin "36") (pinfunction "36_PWM_CLK_CS2_36") (pintype "bidirectional"))
    )
    (net (code "126") (name "unconnected-(U1-37_PWM_CMD_SCK2-Pad37)") (class "Default")
      (node (ref "U1") (pin "37") (pinfunction "37_PWM_CMD_SCK2_37") (pintype "bidirectional"))
    )
    (net (code "127") (name "unconnected-(U1-38_DAT3_RX5-Pad38)") (class "Default")
      (node (ref "U1") (pin "38") (pinfunction "38_DAT3_RX5_38") (pintype "bidirectional"))
    )
    (net (code "128") (name "unconnected-(U1-39_DAT2_TX5-Pad39)") (class "Default")
      (node (ref "U1") (pin "39") (pinfunction "39_DAT2_TX5_39") (pintype "bidirectional"))
    )
    (net (code "129") (name "unconnected-(U1-40_A16_CS1-Pad40)") (class "Default")
      (node (ref "U1") (pin "40") (pinfunction "40_A16_CS1_40") (pintype "bidirectional"))
    )
    (net (code "130") (name "unconnected-(U1-41_A17_MIS01-Pad41)") (class "Default")
      (node (ref "U1") (pin "41") (pinfunction "41_A17_MIS01_41") (pintype "bidirectional"))
    )
    (net (code "131") (name "unconnected-(U1-PadAGND)") (class "Default")
      (node (ref "U1") (pin "AGND") (pinfunction "AGND_AGND") (pintype "bidirectional"))
    )
    (net (code "132") (name "unconnected-(U1-PadGND)") (class "Default")
      (node (ref "U1") (pin "GND") (pinfunction "GND_GND") (pintype "bidirectional"))
    )
    (net (code "133") (name "unconnected-(U3-D-Pad2)") (class "Default")
      (node (ref "U3") (pin "2") (pinfunction "D_2") (pintype "unspecified"))
    )
    (net (code "134") (name "unconnected-(U3-G-Pad1)") (class "Default")
      (node (ref "U3") (pin "1") (pinfunction "G_1") (pintype "unspecified"))
    )
    (net (code "135") (name "unconnected-(U3-S-Pad3)") (class "Default")
      (node (ref "U3") (pin "3") (pinfunction "S_3") (pintype "unspecified"))
    )
    (net (code "136") (name "unconnected-(U5-OUT_+-Pad1)") (class "Default")
      (node (ref "U5") (pin "1") (pinfunction "OUT_+_1") (pintype "unspecified"))
    )
    (net (code "137") (name "unconnected-(U8-Pad1)") (class "Default")
      (node (ref "U8") (pin "1") (pinfunction "1_1") (pintype "unspecified"))
    )
    (net (code "138") (name "unconnected-(U8-Pad2)") (class "Default")
      (node (ref "U8") (pin "2") (pinfunction "2_2") (pintype "unspecified"))
    )
    (net (code "139") (name "unconnected-(U9-NC-Pad11)") (class "Default")
      (node (ref "U9") (pin "11") (pinfunction "NC_11") (pintype "unspecified"))
    )
    (net (code "140") (name "unconnected-(U9-NC-Pad14)") (class "Default")
      (node (ref "U9") (pin "14") (pinfunction "NC_14") (pintype "unspecified"))
    )
  )
)
